# 1s__2023-08-15.net
KiCad netlist of a schematic drawn in Altium Designer
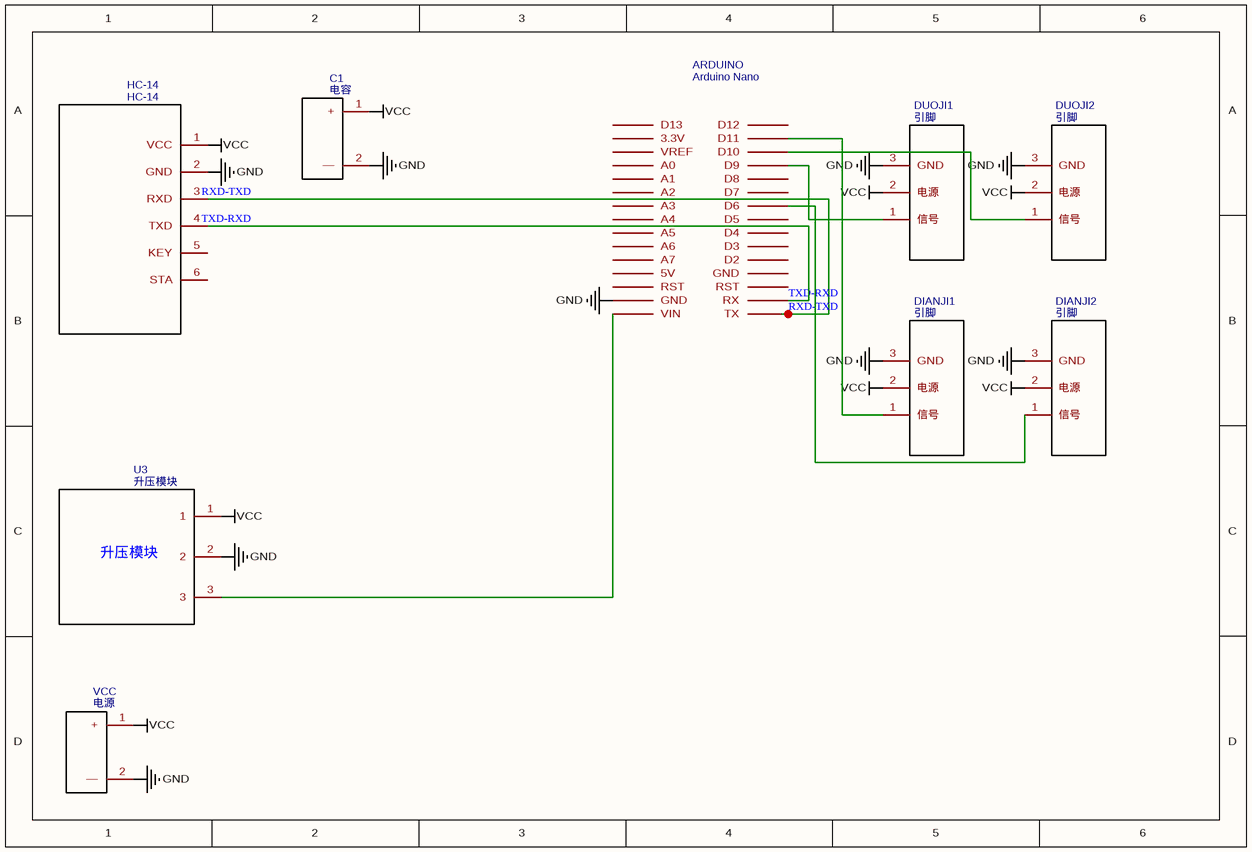
[diagram p0: 1s电池接收电路_2023-08-15.schdoc]

(export (version "E")
  (design (tool "Eeschema 10.0.6"))
  (components
    (comp (ref "ARDUINO")
      (value "Arduino Nano")
      (fields (field (name "CONTRIBUTOR") "jacobadam"))
      (libsource (lib "altium-import") (part "root_0_Arduino Nano_"))
    )
    (comp (ref "C1")
      (value "电容")
      (fields (field (name "CONTRIBUTOR") "jacobadam"))
      (libsource (lib "altium-import") (part "root_0_电容_"))
    )
    (comp (ref "DIANJI1")
      (value "引脚")
      (fields (field (name "CONTRIBUTOR") "jacobadam"))
      (libsource (lib "altium-import") (part "root_2_引脚_"))
    )
    (comp (ref "DIANJI2")
      (value "引脚")
      (fields (field (name "CONTRIBUTOR") "jacobadam"))
      (libsource (lib "altium-import") (part "root_2_引脚_"))
    )
    (comp (ref "DUOJI1")
      (value "引脚")
      (fields (field (name "CONTRIBUTOR") "jacobadam"))
      (libsource (lib "altium-import") (part "root_2_引脚_"))
    )
    (comp (ref "DUOJI2")
      (value "引脚")
      (fields (field (name "CONTRIBUTOR") "jacobadam"))
      (libsource (lib "altium-import") (part "root_2_引脚_"))
    )
    (comp (ref "HC-14")
      (value "HC-14")
      (fields (field (name "CONTRIBUTOR") "jacobadam"))
      (libsource (lib "altium-import") (part "root_0_HC-14_"))
    )
    (comp (ref "U3")
      (value "升压模块")
      (fields (field (name "CONTRIBUTOR") "jacobadam"))
      (libsource (lib "altium-import") (part "root_0_升压模块_"))
    )
    (comp (ref "VCC")
      (value "电源")
      (fields (field (name "CONTRIBUTOR") "jacobadam"))
      (libsource (lib "altium-import") (part "root_0_电源_"))
    )
  )
  (nets
    (net (code "1") (name "/RXD-TXD") (class "Default")
      (node (ref "ARDUINO") (pin "1") (pinfunction "TX_1") (pintype "passive"))
      (node (ref "HC-14") (pin "3") (pinfunction "RXD_3") (pintype "passive"))
    )
    (net (code "2") (name "/TXD-RXD") (class "Default")
      (node (ref "ARDUINO") (pin "2") (pinfunction "RX_2") (pintype "passive"))
      (node (ref "HC-14") (pin "4") (pinfunction "TXD_4") (pintype "passive"))
    )
    (net (code "3") (name "GND") (class "Default")
      (node (ref "ARDUINO") (pin "29") (pinfunction "GND_29") (pintype "passive"))
      (node (ref "C1") (pin "2") (pinfunction "—_2") (pintype "passive"))
      (node (ref "DIANJI1") (pin "3") (pinfunction "GND_3") (pintype "passive"))
      (node (ref "DIANJI2") (pin "3") (pinfunction "GND_3") (pintype "passive"))
      (node (ref "DUOJI1") (pin "3") (pinfunction "GND_3") (pintype "passive"))
      (node (ref "DUOJI2") (pin "3") (pinfunction "GND_3") (pintype "passive"))
      (node (ref "HC-14") (pin "2") (pinfunction "GND_2") (pintype "passive"))
      (node (ref "U3") (pin "2") (pinfunction "2_2") (pintype "passive"))
      (node (ref "VCC") (pin "2") (pinfunction "—_2") (pintype "passive"))
    )
    (net (code "4") (name "Net-(ARDUINO-D6)") (class "Default")
      (node (ref "ARDUINO") (pin "9") (pinfunction "D6_9") (pintype "passive"))
      (node (ref "DIANJI2") (pin "1") (pinfunction "信号_1") (pintype "passive"))
    )
    (net (code "5") (name "Net-(ARDUINO-D9)") (class "Default")
      (node (ref "ARDUINO") (pin "12") (pinfunction "D9_12") (pintype "passive"))
      (node (ref "DUOJI1") (pin "1") (pinfunction "信号_1") (pintype "passive"))
    )
    (net (code "6") (name "Net-(ARDUINO-D10)") (class "Default")
      (node (ref "ARDUINO") (pin "13") (pinfunction "D10_13") (pintype "passive"))
      (node (ref "DUOJI2") (pin "1") (pinfunction "信号_1") (pintype "passive"))
    )
    (net (code "7") (name "Net-(ARDUINO-D11)") (class "Default")
      (node (ref "ARDUINO") (pin "14") (pinfunction "D11_14") (pintype "passive"))
      (node (ref "DIANJI1") (pin "1") (pinfunction "信号_1") (pintype "passive"))
    )
    (net (code "8") (name "Net-(ARDUINO-VIN)") (class "Default")
      (node (ref "ARDUINO") (pin "30") (pinfunction "VIN_30") (pintype "passive"))
      (node (ref "U3") (pin "3") (pinfunction "3_3") (pintype "passive"))
    )
    (net (code "9") (name "VCC") (class "Default")
      (node (ref "C1") (pin "1") (pinfunction "+_1") (pintype "passive"))
      (node (ref "DIANJI1") (pin "2") (pinfunction "电源_2") (pintype "passive"))
      (node (ref "DIANJI2") (pin "2") (pinfunction "电源_2") (pintype "passive"))
      (node (ref "DUOJI1") (pin "2") (pinfunction "电源_2") (pintype "passive"))
      (node (ref "DUOJI2") (pin "2") (pinfunction "电源_2") (pintype "passive"))
      (node (ref "HC-14") (pin "1") (pinfunction "VCC_1") (pintype "passive"))
      (node (ref "U3") (pin "1") (pinfunction "1_1") (pintype "passive"))
      (node (ref "VCC") (pin "1") (pinfunction "+_1") (pintype "passive"))
    )
    (net (code "10") (name "unconnected-(ARDUINO-3.3V-Pad17)") (class "Default")
      (node (ref "ARDUINO") (pin "17") (pinfunction "3.3V_17") (pintype "passive"))
    )
    (net (code "11") (name "unconnected-(ARDUINO-5V-Pad27)") (class "Default")
      (node (ref "ARDUINO") (pin "27") (pinfunction "5V_27") (pintype "passive"))
    )
    (net (code "12") (name "unconnected-(ARDUINO-A0-Pad19)") (class "Default")
      (node (ref "ARDUINO") (pin "19") (pinfunction "A0_19") (pintype "passive"))
    )
    (net (code "13") (name "unconnected-(ARDUINO-A1-Pad20)") (class "Default")
      (node (ref "ARDUINO") (pin "20") (pinfunction "A1_20") (pintype "passive"))
    )
    (net (code "14") (name "unconnected-(ARDUINO-A2-Pad21)") (class "Default")
      (node (ref "ARDUINO") (pin "21") (pinfunction "A2_21") (pintype "passive"))
    )
    (net (code "15") (name "unconnected-(ARDUINO-A3-Pad22)") (class "Default")
      (node (ref "ARDUINO") (pin "22") (pinfunction "A3_22") (pintype "passive"))
    )
    (net (code "16") (name "unconnected-(ARDUINO-A4-Pad23)") (class "Default")
      (node (ref "ARDUINO") (pin "23") (pinfunction "A4_23") (pintype "passive"))
    )
    (net (code "17") (name "unconnected-(ARDUINO-A5-Pad24)") (class "Default")
      (node (ref "ARDUINO") (pin "24") (pinfunction "A5_24") (pintype "passive"))
    )
    (net (code "18") (name "unconnected-(ARDUINO-A6-Pad25)") (class "Default")
      (node (ref "ARDUINO") (pin "25") (pinfunction "A6_25") (pintype "passive"))
    )
    (net (code "19") (name "unconnected-(ARDUINO-A7-Pad26)") (class "Default")
      (node (ref "ARDUINO") (pin "26") (pinfunction "A7_26") (pintype "passive"))
    )
    (net (code "20") (name "unconnected-(ARDUINO-D2-Pad5)") (class "Default")
      (node (ref "ARDUINO") (pin "5") (pinfunction "D2_5") (pintype "passive"))
    )
    (net (code "21") (name "unconnected-(ARDUINO-D3-Pad6)") (class "Default")
      (node (ref "ARDUINO") (pin "6") (pinfunction "D3_6") (pintype "passive"))
    )
    (net (code "22") (name "unconnected-(ARDUINO-D4-Pad7)") (class "Default")
      (node (ref "ARDUINO") (pin "7") (pinfunction "D4_7") (pintype "passive"))
    )
    (net (code "23") (name "unconnected-(ARDUINO-D5-Pad8)") (class "Default")
      (node (ref "ARDUINO") (pin "8") (pinfunction "D5_8") (pintype "passive"))
    )
    (net (code "24") (name "unconnected-(ARDUINO-D7-Pad10)") (class "Default")
      (node (ref "ARDUINO") (pin "10") (pinfunction "D7_10") (pintype "passive"))
    )
    (net (code "25") (name "unconnected-(ARDUINO-D8-Pad11)") (class "Default")
      (node (ref "ARDUINO") (pin "11") (pinfunction "D8_11") (pintype "passive"))
    )
    (net (code "26") (name "unconnected-(ARDUINO-D12-Pad15)") (class "Default")
      (node (ref "ARDUINO") (pin "15") (pinfunction "D12_15") (pintype "passive"))
    )
    (net (code "27") (name "unconnected-(ARDUINO-D13-Pad16)") (class "Default")
      (node (ref "ARDUINO") (pin "16") (pinfunction "D13_16") (pintype "passive"))
    )
    (net (code "28") (name "unconnected-(ARDUINO-GND-Pad4)") (class "Default")
      (node (ref "ARDUINO") (pin "4") (pinfunction "GND_4") (pintype "passive"))
    )
    (net (code "29") (name "unconnected-(ARDUINO-RST-Pad3)") (class "Default")
      (node (ref "ARDUINO") (pin "3") (pinfunction "RST_3") (pintype "passive"))
    )
    (net (code "30") (name "unconnected-(ARDUINO-RST-Pad28)") (class "Default")
      (node (ref "ARDUINO") (pin "28") (pinfunction "RST_28") (pintype "passive"))
    )
    (net (code "31") (name "unconnected-(ARDUINO-VREF-Pad18)") (class "Default")
      (node (ref "ARDUINO") (pin "18") (pinfunction "VREF_18") (pintype "passive"))
    )
    (net (code "32") (name "unconnected-(HC-14-KEY-Pad5)") (class "Default")
      (node (ref "HC-14") (pin "5") (pinfunction "KEY_5") (pintype "passive"))
    )
    (net (code "33") (name "unconnected-(HC-14-STA-Pad6)") (class "Default")
      (node (ref "HC-14") (pin "6") (pinfunction "STA_6") (pintype "passive"))
    )
  )
)
